# gatorBytes_button_board.net
KiCad netlist of a schematic drawn in EAGLE
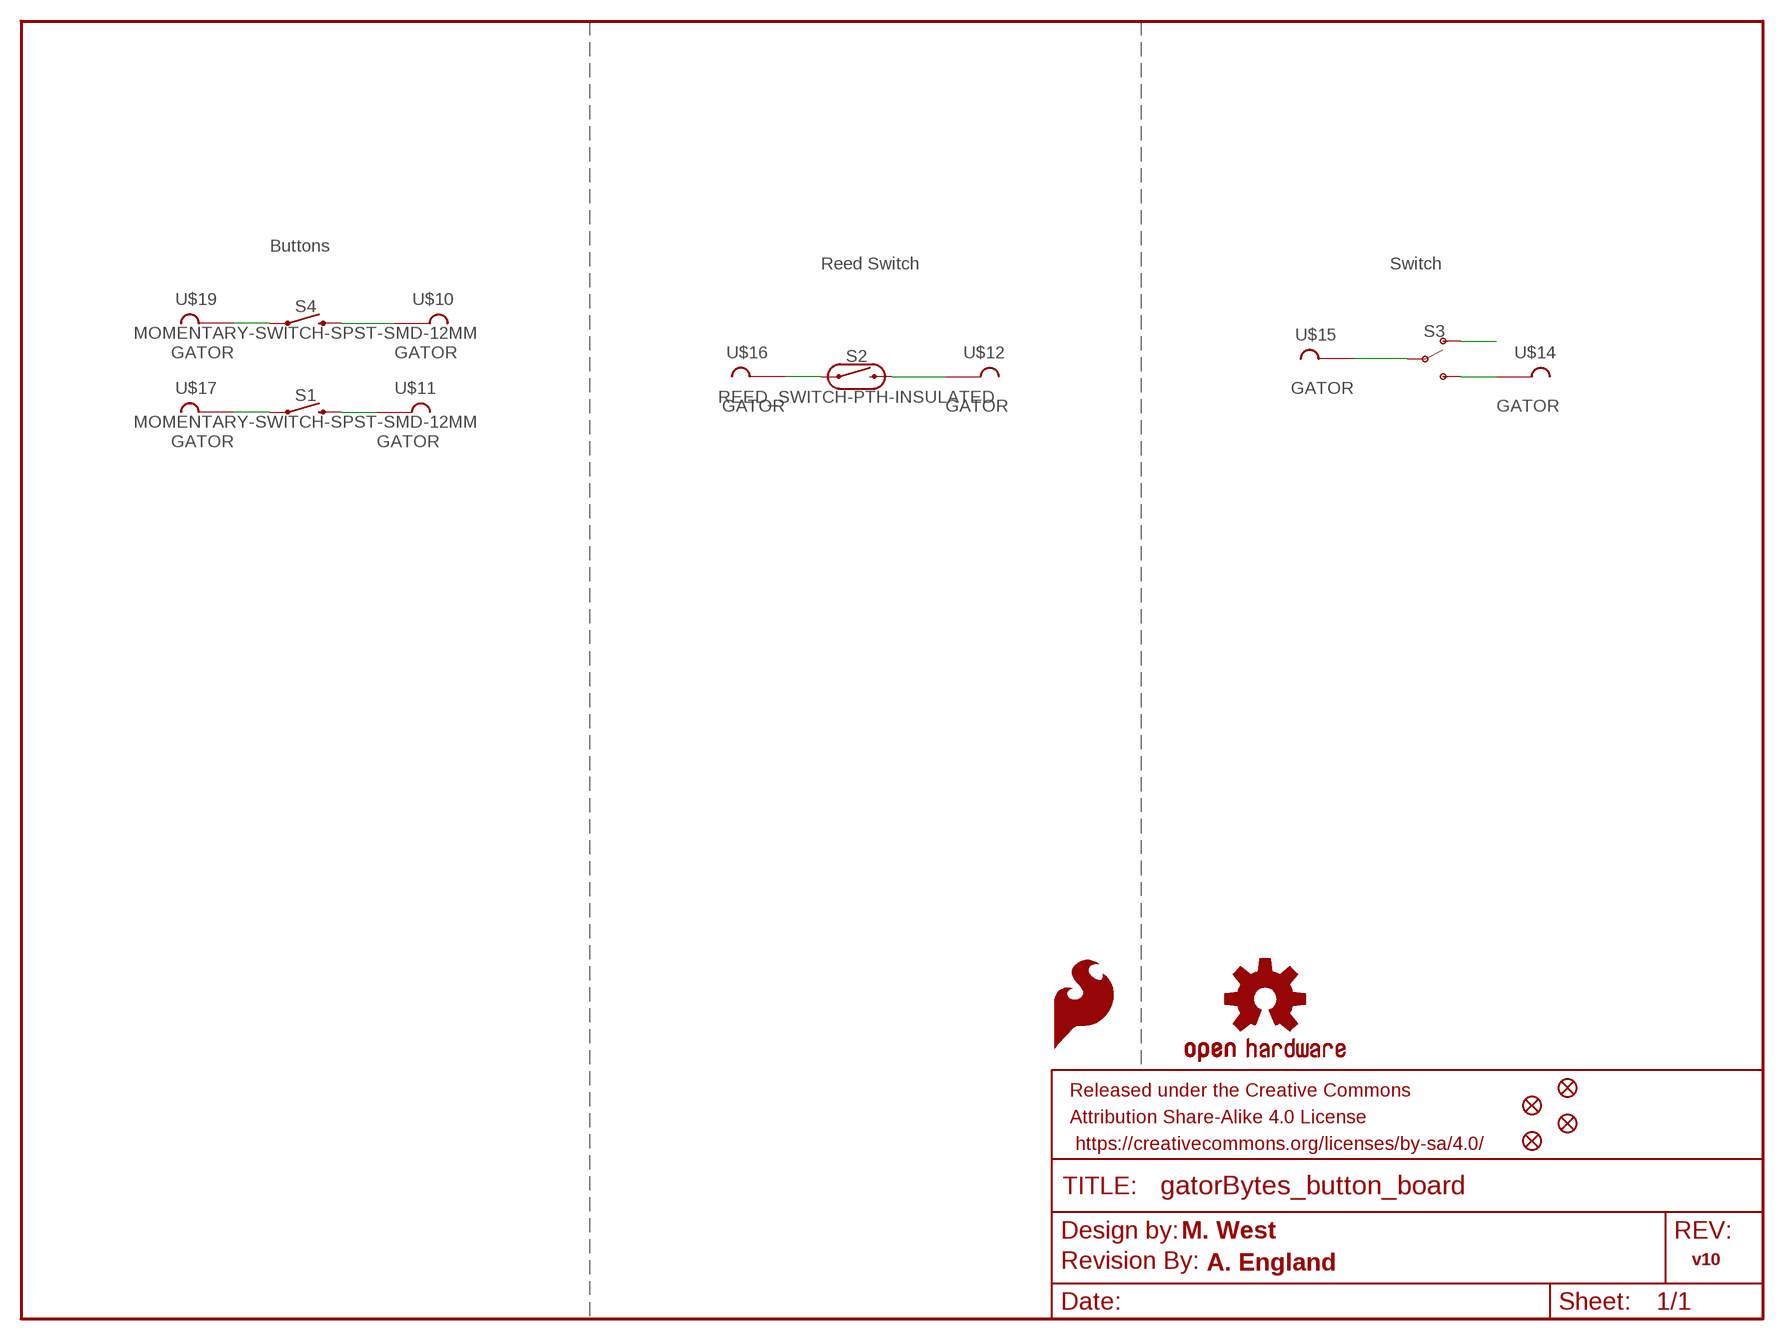
[diagram p0: schematic, sheet 1]

(export (version "E")
  (design (tool "Eeschema 10.0.6"))
  (components
    (comp (ref "FD1")
      (value "FIDUCIALUFIDUCIAL")
      (footprint "eagle-import:FIDUCIAL-MICRO")
      (libsource (lib "eagle-import") (part "FIDUCIALUFIDUCIAL"))
    )
    (comp (ref "FD2")
      (value "FIDUCIALUFIDUCIAL")
      (footprint "eagle-import:FIDUCIAL-MICRO")
      (libsource (lib "eagle-import") (part "FIDUCIALUFIDUCIAL"))
    )
    (comp (ref "FD3")
      (value "FIDUCIALUFIDUCIAL")
      (footprint "eagle-import:FIDUCIAL-MICRO")
      (libsource (lib "eagle-import") (part "FIDUCIALUFIDUCIAL"))
    )
    (comp (ref "FD4")
      (value "FIDUCIALUFIDUCIAL")
      (footprint "eagle-import:FIDUCIAL-MICRO")
      (libsource (lib "eagle-import") (part "FIDUCIALUFIDUCIAL"))
    )
    (comp (ref "FRAME1")
      (value "FRAME-LETTER")
      (footprint "eagle-import:CREATIVE_COMMONS")
      (libsource (lib "eagle-import") (part "FRAME-LETTER"))
    )
    (comp (ref "LOGO1")
      (value "SFE_LOGO_FLAME.1_INCH")
      (footprint "eagle-import:SFE_LOGO_FLAME_.1")
      (libsource (lib "eagle-import") (part "SFE_LOGO_FLAME.1_INCH"))
    )
    (comp (ref "LOGO2")
      (value "OSHW-LOGOS")
      (footprint "eagle-import:OSHW-LOGO-S")
      (libsource (lib "eagle-import") (part "OSHW-LOGOS"))
    )
    (comp (ref "LOGO9")
      (value "REVISION")
      (footprint "eagle-import:REVISION")
      (libsource (lib "eagle-import") (part "REVISION"))
    )
    (comp (ref "S1")
      (value "MOMENTARY-SWITCH-SPST-SMD-12MM")
      (footprint "eagle-import:TACTILE_SWITCH_SMD_12MM")
      (libsource (lib "eagle-import") (part "MOMENTARY-SWITCH-SPST-SMD-12MM"))
    )
    (comp (ref "S2")
      (value "REED_SWITCH-PTH-INSULATED")
      (footprint "eagle-import:REED_SWITCH_PLASTIC")
      (libsource (lib "eagle-import") (part "REED_SWITCH-PTH-INSULATED"))
    )
    (comp (ref "S3")
      (value "SWITCH-SPDT-SMD-AYZ0202")
      (footprint "eagle-import:SWITCH_DPDT_SMD_AYZ0202")
      (libsource (lib "eagle-import") (part "SWITCH-SPDT-SMD-AYZ0202"))
    )
    (comp (ref "S4")
      (value "MOMENTARY-SWITCH-SPST-SMD-12MM")
      (footprint "eagle-import:TACTILE_SWITCH_SMD_12MM")
      (libsource (lib "eagle-import") (part "MOMENTARY-SWITCH-SPST-SMD-12MM"))
    )
    (comp (ref "U$10")
      (value "GATOR")
      (footprint "eagle-import:GATOR")
      (libsource (lib "eagle-import") (part "GATOR"))
    )
    (comp (ref "U$11")
      (value "GATOR")
      (footprint "eagle-import:GATOR")
      (libsource (lib "eagle-import") (part "GATOR"))
    )
    (comp (ref "U$12")
      (value "GATOR")
      (footprint "eagle-import:GATOR")
      (libsource (lib "eagle-import") (part "GATOR"))
    )
    (comp (ref "U$14")
      (value "GATOR")
      (footprint "eagle-import:GATOR")
      (libsource (lib "eagle-import") (part "GATOR"))
    )
    (comp (ref "U$15")
      (value "GATOR")
      (footprint "eagle-import:GATOR")
      (libsource (lib "eagle-import") (part "GATOR"))
    )
    (comp (ref "U$16")
      (value "GATOR")
      (footprint "eagle-import:GATOR")
      (libsource (lib "eagle-import") (part "GATOR"))
    )
    (comp (ref "U$17")
      (value "GATOR")
      (footprint "eagle-import:GATOR")
      (libsource (lib "eagle-import") (part "GATOR"))
    )
    (comp (ref "U$19")
      (value "GATOR")
      (footprint "eagle-import:GATOR")
      (libsource (lib "eagle-import") (part "GATOR"))
    )
  )
  (nets
    (net (code "1") (name "Net-(S1-2)") (class "Default")
      (node (ref "S1") (pin "3") (pinfunction "2_3") (pintype "passive"))
      (node (ref "U$11") (pin "P$1") (pinfunction "P$1_P$1") (pintype "bidirectional"))
      (node (ref "U$11") (pin "P$2") (pinfunction "P$1_P$2") (pintype "bidirectional"))
    )
    (net (code "2") (name "Net-(S1-Pad1)") (class "Default")
      (node (ref "S1") (pin "1") (pinfunction "1_1") (pintype "passive"))
      (node (ref "U$17") (pin "P$1") (pinfunction "P$1_P$1") (pintype "bidirectional"))
      (node (ref "U$17") (pin "P$2") (pinfunction "P$1_P$2") (pintype "bidirectional"))
    )
    (net (code "3") (name "Net-(S2-1)") (class "Default")
      (node (ref "S2") (pin "P$1") (pinfunction "1_P$1") (pintype "passive"))
      (node (ref "U$16") (pin "P$1") (pinfunction "P$1_P$1") (pintype "bidirectional"))
      (node (ref "U$16") (pin "P$2") (pinfunction "P$1_P$2") (pintype "bidirectional"))
    )
    (net (code "4") (name "Net-(S2-2)") (class "Default")
      (node (ref "S2") (pin "P$2") (pinfunction "2_P$2") (pintype "passive"))
      (node (ref "U$12") (pin "P$1") (pinfunction "P$1_P$1") (pintype "bidirectional"))
      (node (ref "U$12") (pin "P$2") (pinfunction "P$1_P$2") (pintype "bidirectional"))
    )
    (net (code "5") (name "Net-(S3-P)") (class "Default")
      (node (ref "S3") (pin "2") (pinfunction "P_2") (pintype "passive"))
      (node (ref "U$15") (pin "P$1") (pinfunction "P$1_P$1") (pintype "bidirectional"))
      (node (ref "U$15") (pin "P$2") (pinfunction "P$1_P$2") (pintype "bidirectional"))
    )
    (net (code "6") (name "Net-(S3-S)") (class "Default")
      (node (ref "S3") (pin "3") (pinfunction "S_3") (pintype "passive"))
      (node (ref "U$14") (pin "P$1") (pinfunction "P$1_P$1") (pintype "bidirectional"))
      (node (ref "U$14") (pin "P$2") (pinfunction "P$1_P$2") (pintype "bidirectional"))
    )
    (net (code "7") (name "Net-(S4-2)") (class "Default")
      (node (ref "S4") (pin "3") (pinfunction "2_3") (pintype "passive"))
      (node (ref "U$10") (pin "P$1") (pinfunction "P$1_P$1") (pintype "bidirectional"))
      (node (ref "U$10") (pin "P$2") (pinfunction "P$1_P$2") (pintype "bidirectional"))
    )
    (net (code "8") (name "Net-(S4-Pad1)") (class "Default")
      (node (ref "S4") (pin "1") (pinfunction "1_1") (pintype "passive"))
      (node (ref "U$19") (pin "P$1") (pinfunction "P$1_P$1") (pintype "bidirectional"))
      (node (ref "U$19") (pin "P$2") (pinfunction "P$1_P$2") (pintype "bidirectional"))
    )
    (net (code "9") (name "unconnected-(S3-O-Pad1)") (class "Default")
      (node (ref "S3") (pin "1") (pinfunction "O_1") (pintype "passive"))
    )
  )
)
